# Arduino_DDS_Shield_Rev_5.net
KiCad netlist of a schematic drawn in Altium Designer
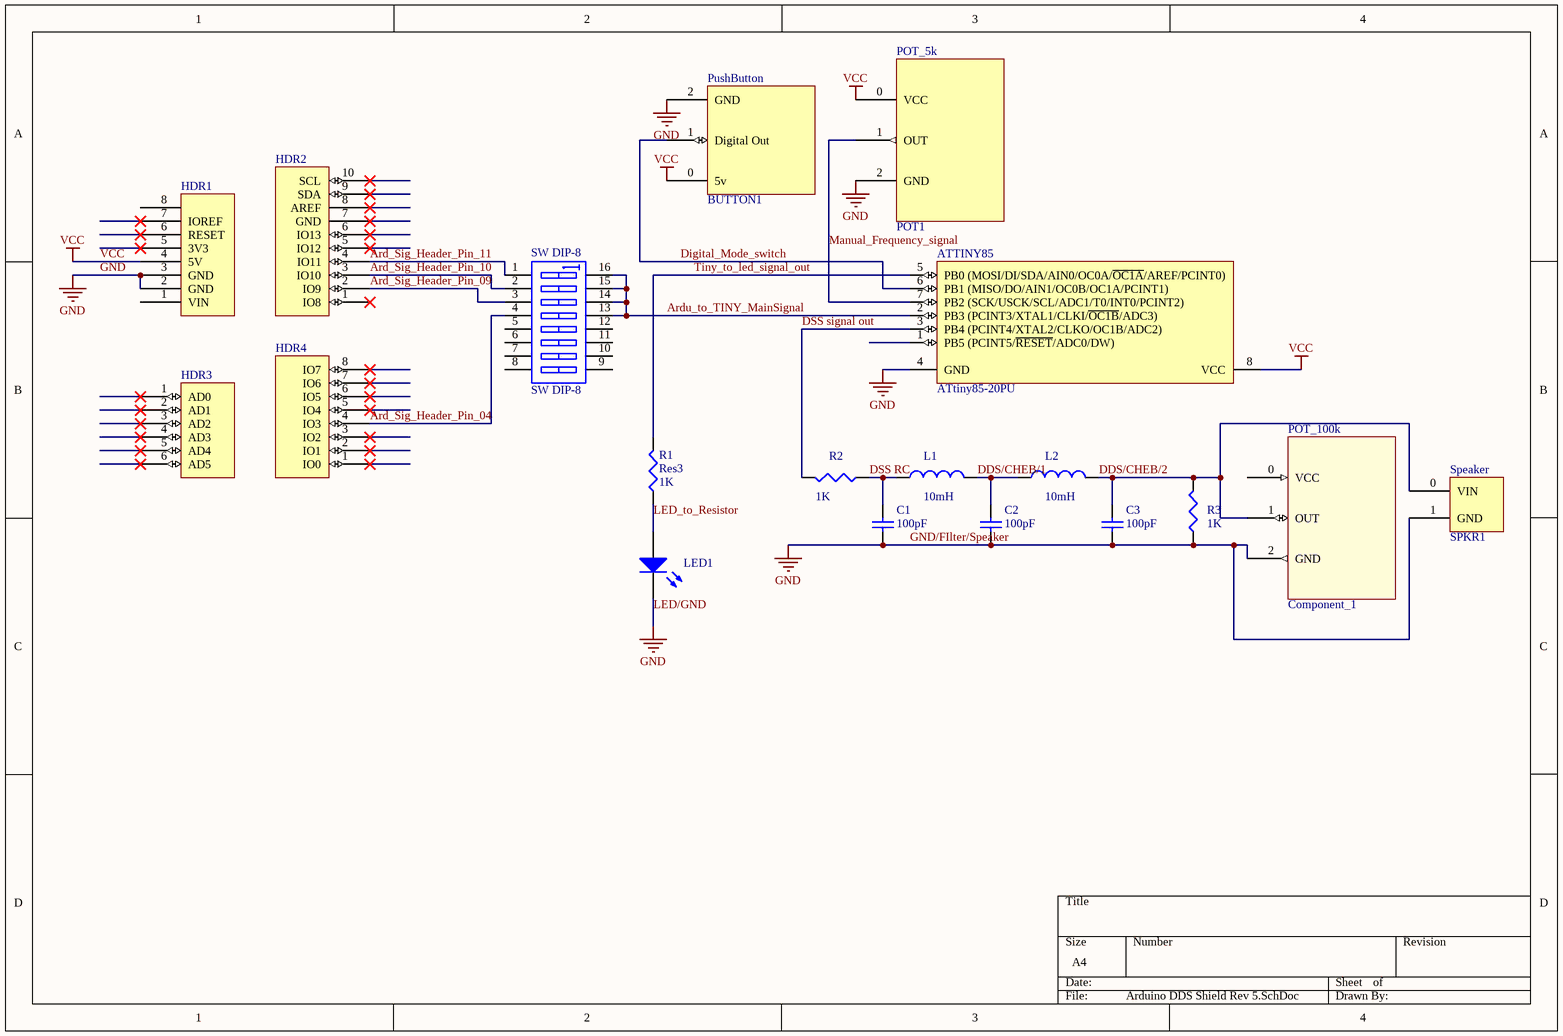
[diagram p0: Arduino DDS Shield Rev 5.SchDoc]

(export (version "E")
  (design (tool "Eeschema 10.0.6"))
  (components
    (comp (ref "ATTINY85")
      (value "ATtiny85-20PU")
      (footprint "8P3")
      (fields (field (name "PUBLISHER") "Altium Limited"))
      (libsource (lib "Atmel Microcontroller 8-Bit tinyAVR") (part "ATtiny85-20PU"))
    )
    (comp (ref "C1")
      (value "100pF")
      (footprint "1608[0603]")
      (description "Capacitor (Semiconductor SIM Model)")
      (fields (field (name "Comment") "Cap Semi") (field (name "PUBLISHER") "Altium Limited"))
      (libsource (lib "Miscellaneous Devices") (part "Cap Semi"))
    )
    (comp (ref "C2")
      (value "100pF")
      (footprint "1608[0603]")
      (description "Capacitor (Semiconductor SIM Model)")
      (fields (field (name "Comment") "Cap Semi") (field (name "PUBLISHER") "Altium Limited"))
      (libsource (lib "Miscellaneous Devices") (part "Cap Semi"))
    )
    (comp (ref "C3")
      (value "100pF")
      (footprint "1608[0603]")
      (description "Capacitor (Semiconductor SIM Model)")
      (fields (field (name "Comment") "Cap Semi") (field (name "PUBLISHER") "Altium Limited"))
      (libsource (lib "Miscellaneous Devices") (part "Cap Semi"))
    )
    (comp (ref "HDR1")
      (value "POWER_UNO")
      (footprint "Header 8x1 8.5mm")
      (libsource (lib "Header") (part "POWER_UNO"))
    )
    (comp (ref "HDR2")
      (value "IOH")
      (footprint "Header:Header 10x1 8.5mm")
      (libsource (lib "Header") (part "IOH"))
    )
    (comp (ref "HDR3")
      (value "AD")
      (footprint "Header:Header 6x1 8.5mm")
      (libsource (lib "Header") (part "AD"))
    )
    (comp (ref "HDR4") (value "IOL") (footprint "Header 8x1 8.5mm") (libsource (lib "Header") (part "IOL")))
    (comp (ref "L1")
      (value "10mH")
      (footprint "AXIAL-0.5")
      (description "Inductor")
      (fields (field (name "PUBLISHER") "Altium Limited"))
      (libsource (lib "Miscellaneous Devices") (part "Inductor"))
    )
    (comp (ref "L2")
      (value "10mH")
      (footprint "AXIAL-0.5")
      (description "Inductor")
      (fields (field (name "PUBLISHER") "Altium Limited"))
      (libsource (lib "Miscellaneous Devices") (part "Inductor"))
    )
    (comp (ref "LED1")
      (value "LED1")
      (footprint "LED-1")
      (description "Typical RED GaAs LED")
      (fields (field (name "PUBLISHER") "Altium Limited"))
      (libsource (lib "Miscellaneous Devices") (part "LED1"))
    )
    (comp (ref "POT_5k")
      (value "POT1")
      (footprint "Pot5k")
      (description "5k RES")
      (libsource (lib "PotLib_Rev_5") (part "Component_1"))
    )
    (comp (ref "POT_100k")
      (value "Component_1")
      (footprint "pot100k")
      (description "5k RES")
      (libsource (lib "PotLib_v_2") (part "Component_1"))
    )
    (comp (ref "PushButton")
      (value "BUTTON1")
      (footprint "PushButtonFrame")
      (libsource (lib "Pushbutton_V_5") (part "PushButton"))
    )
    (comp (ref "R1")
      (value "Res3")
      (footprint "J1-0603")
      (description "Resistor")
      (fields (field (name "ALTIUM_VALUE") "1K") (field (name "PUBLISHER") "Altium Limited"))
      (libsource (lib "Miscellaneous Devices") (part "Res3"))
    )
    (comp (ref "R2")
      (value "1K")
      (footprint "J1-0603")
      (description "Resistor")
      (fields (field (name "Comment") "Res3") (field (name "PUBLISHER") "Altium Limited"))
      (libsource (lib "Miscellaneous Devices") (part "Res3"))
    )
    (comp (ref "R3")
      (value "1K")
      (footprint "J1-0603")
      (description "Resistor")
      (fields (field (name "Comment") "Res3") (field (name "PUBLISHER") "Altium Limited"))
      (libsource (lib "Miscellaneous Devices") (part "Res3"))
    )
    (comp (ref "Speaker")
      (value "SPKR1")
      (footprint "PCBComponent_1")
      (libsource (lib "Schlib1_rev_01") (part "Component_1"))
    )
    (comp (ref "SW DIP-8")
      (value "SW DIP-8")
      (footprint "DIP8posSolder")
      (description "DIP Switch, 8 Position, SPST")
      (fields (field (name "PUBLISHER") "Altium Limited"))
      (libsource (lib "Miscellaneous Devices") (part "SW DIP-8"))
    )
  )
  (nets
    (net (code "2") (name "/Ard_Sig_Header_Pin_04") (class "Default")
      (node (ref "HDR4") (pin "4") (pinfunction "IO3_4") (pintype "bidirectional"))
      (node (ref "SW DIP-8") (pin "4") (pinfunction "A4_4") (pintype "passive"))
    )
    (net (code "3") (name "/Ard_Sig_Header_Pin_09") (class "Default")
      (node (ref "HDR2") (pin "2") (pinfunction "IO9_2") (pintype "bidirectional"))
      (node (ref "SW DIP-8") (pin "3") (pinfunction "A3_3") (pintype "passive"))
    )
    (net (code "4") (name "/Ard_Sig_Header_Pin_10") (class "Default")
      (node (ref "HDR2") (pin "3") (pinfunction "IO10_3") (pintype "bidirectional"))
      (node (ref "SW DIP-8") (pin "2") (pinfunction "A2_2") (pintype "passive"))
    )
    (net (code "5") (name "/Ard_Sig_Header_Pin_11") (class "Default")
      (node (ref "HDR2") (pin "4") (pinfunction "IO11_4") (pintype "bidirectional"))
      (node (ref "SW DIP-8") (pin "1") (pinfunction "A1_1") (pintype "passive"))
    )
    (net (code "6") (name "/Ardu_to_TINY_MainSignal") (class "Default")
      (node (ref "ATTINY85") (pin "2") (pinfunction "PB3_(PCINT3/XTAL1/CLKI/~{OC1B}/ADC3)_2") (pintype "bidirectional"))
      (node (ref "SW DIP-8") (pin "13") (pinfunction "B4_13") (pintype "passive"))
      (node (ref "SW DIP-8") (pin "14") (pinfunction "B3_14") (pintype "passive"))
      (node (ref "SW DIP-8") (pin "15") (pinfunction "B2_15") (pintype "passive"))
      (node (ref "SW DIP-8") (pin "16") (pinfunction "B1_16") (pintype "passive"))
    )
    (net (code "7") (name "/DDS{slash}CHEB{slash}1") (class "Default")
      (node (ref "C2") (pin "2") (pinfunction "2_2") (pintype "passive"))
      (node (ref "L1") (pin "2") (pinfunction "2_2") (pintype "passive"))
      (node (ref "L2") (pin "1") (pinfunction "1_1") (pintype "passive"))
    )
    (net (code "8") (name "/DDS{slash}CHEB{slash}2") (class "Default")
      (node (ref "C3") (pin "2") (pinfunction "2_2") (pintype "passive"))
      (node (ref "L2") (pin "2") (pinfunction "2_2") (pintype "passive"))
      (node (ref "POT_100k") (pin "1") (pinfunction "OUT_1") (pintype "bidirectional"))
      (node (ref "R3") (pin "2") (pinfunction "2_2") (pintype "passive"))
      (node (ref "Speaker") (pin "0") (pinfunction "VIN_0") (pintype "power_in"))
    )
    (net (code "9") (name "/DSS RC") (class "Default")
      (node (ref "C1") (pin "2") (pinfunction "2_2") (pintype "passive"))
      (node (ref "L1") (pin "1") (pinfunction "1_1") (pintype "passive"))
      (node (ref "R2") (pin "1") (pinfunction "1_1") (pintype "passive"))
    )
    (net (code "10") (name "/DSS signal out") (class "Default")
      (node (ref "ATTINY85") (pin "3") (pinfunction "PB4_(PCINT4/XTAL2/CLKO/OC1B/ADC2)_3") (pintype "bidirectional"))
      (node (ref "R2") (pin "2") (pinfunction "2_2") (pintype "passive"))
    )
    (net (code "11") (name "/Digital_Mode_switch") (class "Default")
      (node (ref "ATTINY85") (pin "6") (pinfunction "PB1_(MISO/DO/AIN1/OC0B/OC1A/PCINT1)_6") (pintype "bidirectional"))
      (node (ref "PushButton") (pin "1") (pinfunction "Digital_Out_1") (pintype "bidirectional"))
    )
    (net (code "12") (name "/LED_to_Resistor") (class "Default")
      (node (ref "LED1") (pin "1") (pinfunction "A_1") (pintype "passive"))
      (node (ref "R1") (pin "1") (pinfunction "1_1") (pintype "passive"))
    )
    (net (code "13") (name "/Manual_Frequency_signal") (class "Default")
      (node (ref "ATTINY85") (pin "7") (pinfunction "PB2_(SCK/USCK/SCL/ADC1/T0/INT0/PCINT2)_7") (pintype "bidirectional"))
      (node (ref "POT_5k") (pin "1") (pinfunction "OUT_1") (pintype "output"))
    )
    (net (code "14") (name "/Tiny_to_led_signal_out") (class "Default")
      (node (ref "ATTINY85") (pin "5") (pinfunction "PB0_(MOSI/DI/SDA/AIN0/OC0A/~{OC1A}/AREF/PCINT0)_5") (pintype "bidirectional"))
      (node (ref "R1") (pin "2") (pinfunction "2_2") (pintype "passive"))
    )
    (net (code "15") (name "GND") (class "Default")
      (node (ref "ATTINY85") (pin "4") (pinfunction "GND_4") (pintype "power_in"))
      (node (ref "C1") (pin "1") (pinfunction "1_1") (pintype "passive"))
      (node (ref "C2") (pin "1") (pinfunction "1_1") (pintype "passive"))
      (node (ref "C3") (pin "1") (pinfunction "1_1") (pintype "passive"))
      (node (ref "HDR1") (pin "2") (pinfunction "GND_2") (pintype "power_in"))
      (node (ref "HDR1") (pin "3") (pinfunction "GND_3") (pintype "power_in"))
      (node (ref "LED1") (pin "2") (pinfunction "K_2") (pintype "passive"))
      (node (ref "POT_100k") (pin "2") (pinfunction "GND_2") (pintype "output"))
      (node (ref "POT_5k") (pin "2") (pinfunction "GND_2") (pintype "power_in"))
      (node (ref "PushButton") (pin "2") (pinfunction "GND_2") (pintype "power_in"))
      (node (ref "R3") (pin "1") (pinfunction "1_1") (pintype "passive"))
      (node (ref "Speaker") (pin "1") (pinfunction "GND_1") (pintype "power_in"))
    )
    (net (code "16") (name "VCC") (class "Default")
      (node (ref "ATTINY85") (pin "8") (pinfunction "VCC_8") (pintype "power_in"))
      (node (ref "HDR1") (pin "4") (pinfunction "5V_4") (pintype "power_in"))
      (node (ref "POT_5k") (pin "0") (pinfunction "VCC_0") (pintype "power_in"))
      (node (ref "PushButton") (pin "0") (pinfunction "5v_0") (pintype "power_in"))
    )
    (net (code "17") (name "unconnected-(ATTINY85-PB5_(PCINT5{slash}~{RESET}{slash}ADC0{slash}DW)-Pad1)") (class "Default")
      (node (ref "ATTINY85") (pin "1") (pinfunction "PB5_(PCINT5/~{RESET}/ADC0/DW)_1") (pintype "bidirectional"))
    )
    (net (code "18") (name "unconnected-(HDR1-3V3-Pad5)") (class "Default")
      (node (ref "HDR1") (pin "5") (pinfunction "3V3_5") (pintype "power_in+no_connect"))
    )
    (net (code "19") (name "unconnected-(HDR1-IOREF-Pad7)") (class "Default")
      (node (ref "HDR1") (pin "7") (pinfunction "IOREF_7") (pintype "power_in+no_connect"))
    )
    (net (code "20") (name "unconnected-(HDR1-Pad8)") (class "Default")
      (node (ref "HDR1") (pin "8") (pintype "passive"))
    )
    (net (code "21") (name "unconnected-(HDR1-RESET-Pad6)") (class "Default")
      (node (ref "HDR1") (pin "6") (pinfunction "RESET_6") (pintype "passive+no_connect"))
    )
    (net (code "22") (name "unconnected-(HDR1-VIN-Pad1)") (class "Default")
      (node (ref "HDR1") (pin "1") (pinfunction "VIN_1") (pintype "power_in"))
    )
    (net (code "23") (name "unconnected-(HDR2-AREF-Pad8)") (class "Default")
      (node (ref "HDR2") (pin "8") (pinfunction "AREF_8") (pintype "passive+no_connect"))
    )
    (net (code "24") (name "unconnected-(HDR2-GND-Pad7)") (class "Default")
      (node (ref "HDR2") (pin "7") (pinfunction "GND_7") (pintype "power_in+no_connect"))
    )
    (net (code "25") (name "unconnected-(HDR2-IO8-Pad1)") (class "Default")
      (node (ref "HDR2") (pin "1") (pinfunction "IO8_1") (pintype "bidirectional+no_connect"))
    )
    (net (code "26") (name "unconnected-(HDR2-IO12-Pad5)") (class "Default")
      (node (ref "HDR2") (pin "5") (pinfunction "IO12_5") (pintype "bidirectional+no_connect"))
    )
    (net (code "27") (name "unconnected-(HDR2-IO13-Pad6)") (class "Default")
      (node (ref "HDR2") (pin "6") (pinfunction "IO13_6") (pintype "bidirectional+no_connect"))
    )
    (net (code "28") (name "unconnected-(HDR2-SCL-Pad10)") (class "Default")
      (node (ref "HDR2") (pin "10") (pinfunction "SCL_10") (pintype "bidirectional+no_connect"))
    )
    (net (code "29") (name "unconnected-(HDR2-SDA-Pad9)") (class "Default")
      (node (ref "HDR2") (pin "9") (pinfunction "SDA_9") (pintype "bidirectional+no_connect"))
    )
    (net (code "30") (name "unconnected-(HDR3-AD0-Pad1)") (class "Default")
      (node (ref "HDR3") (pin "1") (pinfunction "AD0_1") (pintype "bidirectional+no_connect"))
    )
    (net (code "31") (name "unconnected-(HDR3-AD1-Pad2)") (class "Default")
      (node (ref "HDR3") (pin "2") (pinfunction "AD1_2") (pintype "bidirectional+no_connect"))
    )
    (net (code "32") (name "unconnected-(HDR3-AD2-Pad3)") (class "Default")
      (node (ref "HDR3") (pin "3") (pinfunction "AD2_3") (pintype "bidirectional+no_connect"))
    )
    (net (code "33") (name "unconnected-(HDR3-AD3-Pad4)") (class "Default")
      (node (ref "HDR3") (pin "4") (pinfunction "AD3_4") (pintype "bidirectional+no_connect"))
    )
    (net (code "34") (name "unconnected-(HDR3-AD4-Pad5)") (class "Default")
      (node (ref "HDR3") (pin "5") (pinfunction "AD4_5") (pintype "bidirectional+no_connect"))
    )
    (net (code "35") (name "unconnected-(HDR3-AD5-Pad6)") (class "Default")
      (node (ref "HDR3") (pin "6") (pinfunction "AD5_6") (pintype "bidirectional+no_connect"))
    )
    (net (code "36") (name "unconnected-(HDR4-IO0-Pad1)") (class "Default")
      (node (ref "HDR4") (pin "1") (pinfunction "IO0_1") (pintype "bidirectional+no_connect"))
    )
    (net (code "37") (name "unconnected-(HDR4-IO1-Pad2)") (class "Default")
      (node (ref "HDR4") (pin "2") (pinfunction "IO1_2") (pintype "bidirectional+no_connect"))
    )
    (net (code "38") (name "unconnected-(HDR4-IO2-Pad3)") (class "Default")
      (node (ref "HDR4") (pin "3") (pinfunction "IO2_3") (pintype "bidirectional+no_connect"))
    )
    (net (code "39") (name "unconnected-(HDR4-IO4-Pad5)") (class "Default")
      (node (ref "HDR4") (pin "5") (pinfunction "IO4_5") (pintype "bidirectional+no_connect"))
    )
    (net (code "40") (name "unconnected-(HDR4-IO5-Pad6)") (class "Default")
      (node (ref "HDR4") (pin "6") (pinfunction "IO5_6") (pintype "bidirectional+no_connect"))
    )
    (net (code "41") (name "unconnected-(HDR4-IO6-Pad7)") (class "Default")
      (node (ref "HDR4") (pin "7") (pinfunction "IO6_7") (pintype "bidirectional+no_connect"))
    )
    (net (code "42") (name "unconnected-(HDR4-IO7-Pad8)") (class "Default")
      (node (ref "HDR4") (pin "8") (pinfunction "IO7_8") (pintype "bidirectional+no_connect"))
    )
    (net (code "43") (name "unconnected-(POT_100k-VCC-Pad0)") (class "Default")
      (node (ref "POT_100k") (pin "0") (pinfunction "VCC_0") (pintype "input"))
    )
    (net (code "44") (name "unconnected-(SW DIP-8-A5-Pad5)") (class "Default")
      (node (ref "SW DIP-8") (pin "5") (pinfunction "A5_5") (pintype "passive"))
    )
    (net (code "45") (name "unconnected-(SW DIP-8-A6-Pad6)") (class "Default")
      (node (ref "SW DIP-8") (pin "6") (pinfunction "A6_6") (pintype "passive"))
    )
    (net (code "46") (name "unconnected-(SW DIP-8-A7-Pad7)") (class "Default")
      (node (ref "SW DIP-8") (pin "7") (pinfunction "A7_7") (pintype "passive"))
    )
    (net (code "47") (name "unconnected-(SW DIP-8-A8-Pad8)") (class "Default")
      (node (ref "SW DIP-8") (pin "8") (pinfunction "A8_8") (pintype "passive"))
    )
    (net (code "48") (name "unconnected-(SW DIP-8-B5-Pad12)") (class "Default")
      (node (ref "SW DIP-8") (pin "12") (pinfunction "B5_12") (pintype "passive"))
    )
    (net (code "49") (name "unconnected-(SW DIP-8-B6-Pad11)") (class "Default")
      (node (ref "SW DIP-8") (pin "11") (pinfunction "B6_11") (pintype "passive"))
    )
    (net (code "50") (name "unconnected-(SW DIP-8-B7-Pad10)") (class "Default")
      (node (ref "SW DIP-8") (pin "10") (pinfunction "B7_10") (pintype "passive"))
    )
    (net (code "51") (name "unconnected-(SW DIP-8-B8-Pad9)") (class "Default")
      (node (ref "SW DIP-8") (pin "9") (pinfunction "B8_9") (pintype "passive"))
    )
  )
)
